# SecurityNode.net
KiCad netlist of a schematic drawn in Altium Designer
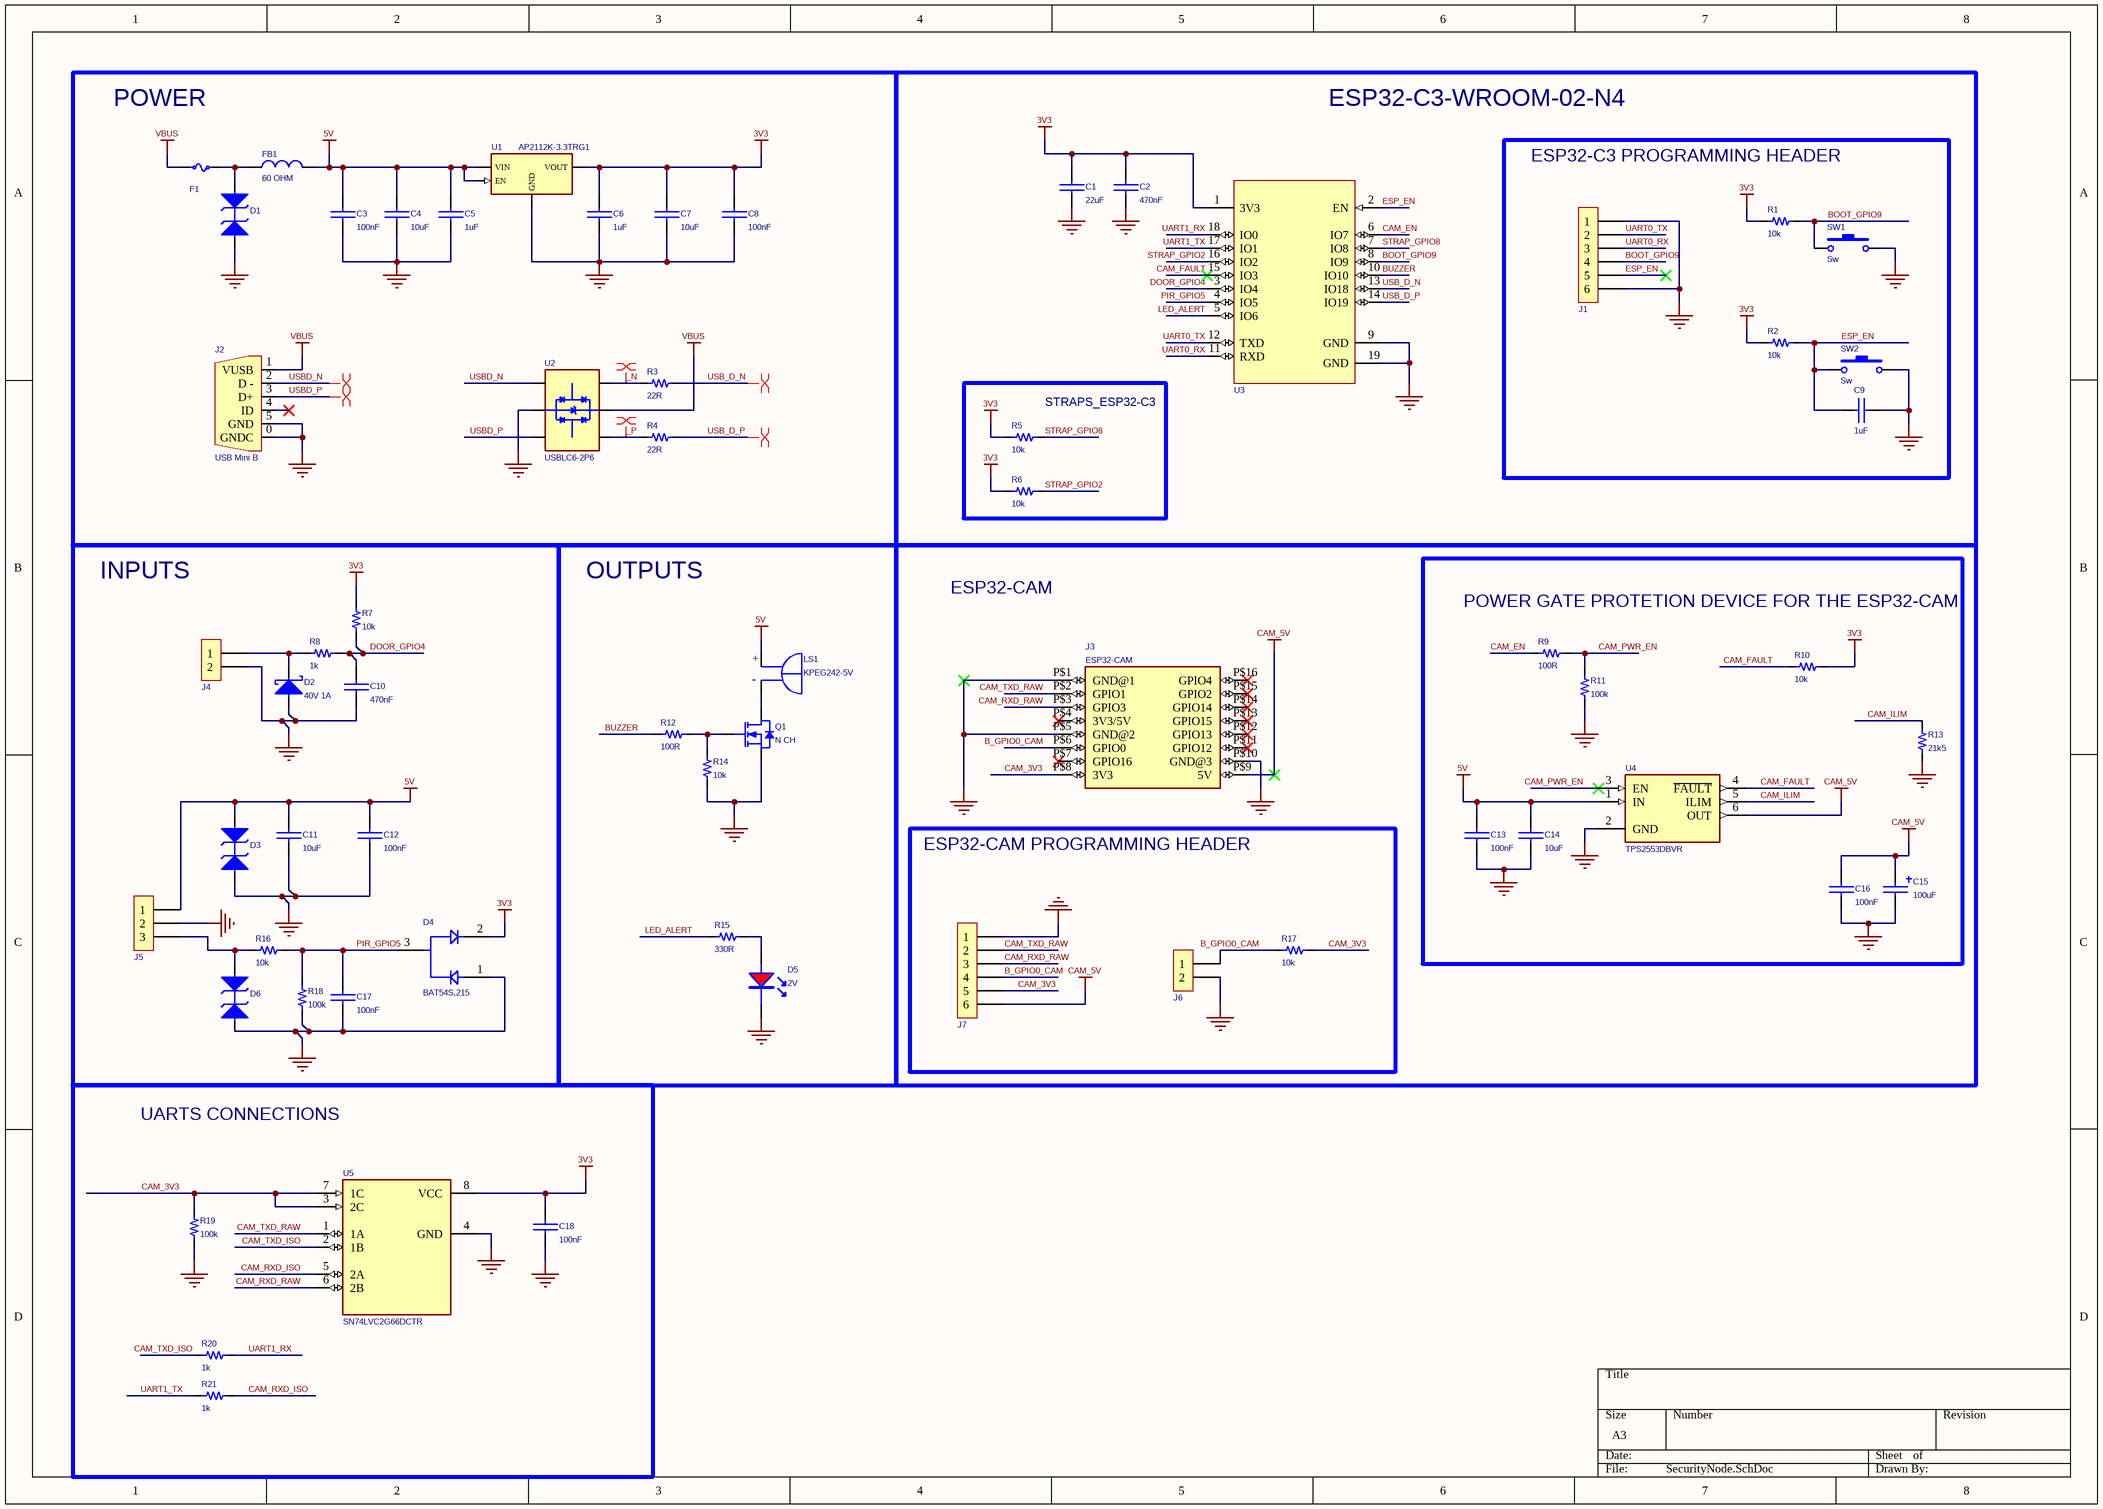
[diagram p0: SecurityNode.SchDoc]

(export (version "E")
  (design (tool "Eeschema 10.0.6"))
  (components
    (comp (ref "C1")
      (value "22uF")
      (footprint "0805_cap")
      (description "16V 22uF X5R ±20% 0805 Multilayer Ceramic Capacitors MLCC - SMD/SMT ROHS")
      (fields
        (field (name "MANUFACTURER") "Chinocera")
        (field (name "MANUFACTURER PART NUMBER") "HGC0805R5226M160NSLJ")
      )
      (libsource (lib "SecurityNodeComponents") (part "Cap_22uF_0805_16V"))
    )
    (comp (ref "C2")
      (value "470nF")
      (footprint "0603_cap")
      (description "50V 470nF X7R ±10% 0603 Multilayer Ceramic Capacitors MLCC - SMD/SMT ROHS")
      (fields
        (field (name "MANUFACTURER") "Chinocera")
        (field (name "MANUFACTURER PART NUMBER") "HGC0603R7474K500NTHJ")
      )
      (libsource (lib "SecurityNodeComponents") (part "Cap_470nF_0603_50V"))
    )
    (comp (ref "C3")
      (value "100nF")
      (footprint "0603_cap")
      (description "100nF ±20% 6.3V Ceramic Capacitor X5R 0201")
      (fields
        (field (name "MANUFACTURER") "HRE")
        (field (name "MANUFACTURER PART NUMBER") "CGA0201X5R104M6R3ET")
      )
      (libsource (lib "SecurityNodeComponents") (part "Cap_100nF_0603_6.3V"))
    )
    (comp (ref "C4")
      (value "10uF")
      (footprint "0603_cap")
      (description "10V 10uF X5R ±10% 0603 Multilayer Ceramic Capacitors MLCC - SMD/SMT ROHS")
      (fields
        (field (name "MANUFACTURER") "CCTC")
        (field (name "MANUFACTURER PART NUMBER") "TCC0603X5R106K100CT")
      )
      (libsource (lib "SecurityNodeComponents") (part "Cap_10uF_0603_10V"))
    )
    (comp (ref "C5")
      (value "1uF")
      (footprint "0603_cap")
      (description "50V 1uF X5R ±10% 0603 Multilayer Ceramic Capacitors MLCC - SMD/SMT ROHS")
      (fields
        (field (name "MANUFACTURER") "Samsung Electro-Mechanics")
        (field (name "MANUFACTURER PART NUMBER") "CL10A105KB8NNNC")
      )
      (libsource (lib "SecurityNodeComponents") (part "Cap_1uF_0603_50V"))
    )
    (comp (ref "C6")
      (value "1uF")
      (footprint "0603_cap")
      (description "50V 1uF X5R ±10% 0603 Multilayer Ceramic Capacitors MLCC - SMD/SMT ROHS")
      (fields
        (field (name "MANUFACTURER") "Samsung Electro-Mechanics")
        (field (name "MANUFACTURER PART NUMBER") "CL10A105KB8NNNC")
      )
      (libsource (lib "SecurityNodeComponents") (part "Cap_1uF_0603_50V"))
    )
    (comp (ref "C7")
      (value "10uF")
      (footprint "0603_cap")
      (description "10V 10uF X5R ±10% 0603 Multilayer Ceramic Capacitors MLCC - SMD/SMT ROHS")
      (fields
        (field (name "MANUFACTURER") "CCTC")
        (field (name "MANUFACTURER PART NUMBER") "TCC0603X5R106K100CT")
      )
      (libsource (lib "SecurityNodeComponents") (part "Cap_10uF_0603_10V"))
    )
    (comp (ref "C8")
      (value "100nF")
      (footprint "0603_cap")
      (description "100nF ±20% 6.3V Ceramic Capacitor X5R 0201")
      (fields
        (field (name "MANUFACTURER") "HRE")
        (field (name "MANUFACTURER PART NUMBER") "CGA0201X5R104M6R3ET")
      )
      (libsource (lib "SecurityNodeComponents") (part "Cap_100nF_0603_6.3V"))
    )
    (comp (ref "C9")
      (value "1uF")
      (footprint "0603_cap")
      (description "50V 1uF X5R ±10% 0603 Multilayer Ceramic Capacitors MLCC - SMD/SMT ROHS")
      (fields
        (field (name "MANUFACTURER") "Samsung Electro-Mechanics")
        (field (name "MANUFACTURER PART NUMBER") "CL10A105KB8NNNC")
      )
      (libsource (lib "SecurityNodeComponents") (part "Cap_1uF_0603_50V"))
    )
    (comp (ref "C10")
      (value "470nF")
      (footprint "0603_cap")
      (description "50V 470nF X7R ±10% 0603 Multilayer Ceramic Capacitors MLCC - SMD/SMT ROHS")
      (fields
        (field (name "MANUFACTURER") "Chinocera")
        (field (name "MANUFACTURER PART NUMBER") "HGC0603R7474K500NTHJ")
      )
      (libsource (lib "SecurityNodeComponents") (part "Cap_470nF_0603_50V"))
    )
    (comp (ref "C11")
      (value "10uF")
      (footprint "0603_cap")
      (description "10V 10uF X5R ±10% 0603 Multilayer Ceramic Capacitors MLCC - SMD/SMT ROHS")
      (fields
        (field (name "MANUFACTURER") "CCTC")
        (field (name "MANUFACTURER PART NUMBER") "TCC0603X5R106K100CT")
      )
      (libsource (lib "SecurityNodeComponents") (part "Cap_10uF_0603_10V"))
    )
    (comp (ref "C12")
      (value "100nF")
      (footprint "0603_cap")
      (description "100nF ±20% 6.3V Ceramic Capacitor X5R 0201")
      (fields
        (field (name "MANUFACTURER") "HRE")
        (field (name "MANUFACTURER PART NUMBER") "CGA0201X5R104M6R3ET")
      )
      (libsource (lib "SecurityNodeComponents") (part "Cap_100nF_0603_6.3V"))
    )
    (comp (ref "C13")
      (value "100nF")
      (footprint "0603_cap")
      (description "100nF ±20% 6.3V Ceramic Capacitor X5R 0201")
      (fields
        (field (name "MANUFACTURER") "HRE")
        (field (name "MANUFACTURER PART NUMBER") "CGA0201X5R104M6R3ET")
      )
      (libsource (lib "SecurityNodeComponents") (part "Cap_100nF_0603_6.3V"))
    )
    (comp (ref "C14")
      (value "10uF")
      (footprint "0603_cap")
      (description "10V 10uF X5R ±10% 0603 Multilayer Ceramic Capacitors MLCC - SMD/SMT ROHS")
      (fields
        (field (name "MANUFACTURER") "CCTC")
        (field (name "MANUFACTURER PART NUMBER") "TCC0603X5R106K100CT")
      )
      (libsource (lib "SecurityNodeComponents") (part "Cap_10uF_0603_10V"))
    )
    (comp (ref "C15")
      (value "100uF")
      (footprint "CAP_TH_2.5MM_6.3*12MM")
      (description "100uF 35V ±20% Plugin,D6.3xL12mm Aluminum Electrolytic Capacitors - Leaded ROHS")
      (fields (field (name "MANUFACTURER") "HRK") (field (name "MANUFACTURER PART NUMBER") "35V100uF CD110"))
      (libsource (lib "SecurityNodeComponents") (part "Cap_100uF_ALU_TH_35V"))
    )
    (comp (ref "C16")
      (value "100nF")
      (footprint "0603_cap")
      (description "100nF ±20% 6.3V Ceramic Capacitor X5R 0201")
      (fields
        (field (name "MANUFACTURER") "HRE")
        (field (name "MANUFACTURER PART NUMBER") "CGA0201X5R104M6R3ET")
      )
      (libsource (lib "SecurityNodeComponents") (part "Cap_100nF_0603_6.3V"))
    )
    (comp (ref "C17")
      (value "100nF")
      (footprint "0603_cap")
      (description "100nF ±20% 6.3V Ceramic Capacitor X5R 0201")
      (fields
        (field (name "MANUFACTURER") "HRE")
        (field (name "MANUFACTURER PART NUMBER") "CGA0201X5R104M6R3ET")
      )
      (libsource (lib "SecurityNodeComponents") (part "Cap_100nF_0603_6.3V"))
    )
    (comp (ref "C18")
      (value "100nF")
      (footprint "0603_cap")
      (description "100nF ±20% 6.3V Ceramic Capacitor X5R 0201")
      (fields
        (field (name "MANUFACTURER") "HRE")
        (field (name "MANUFACTURER PART NUMBER") "CGA0201X5R104M6R3ET")
      )
      (libsource (lib "SecurityNodeComponents") (part "Cap_100nF_0603_6.3V"))
    )
    (comp (ref "D1")
      (value "TVS 12V")
      (footprint "SOD_123FL")
      (description "21.7A 200W@10/1000us 9.2V 7V Bidirectional 5V SOD-123FL ESD and Surge Protection (TVS/ESD) ROHS")
      (fields (field (name "MANUFACTURER") "TDSEMIC") (field (name "MANUFACTURER PART NUMBER") "SMF5.0CA"))
      (libsource (lib "SecurityNodeComponents") (part "TVS_5V_1CH_BID_SOD_123FL"))
    )
    (comp (ref "D2")
      (value "40V 1A")
      (footprint "SOD_123")
      (description "DIODE SCHOTTKY 40V 1A SOD123F")
      (fields
        (field (name "MANUFACTURER") "Shanghai Prisemi Elec")
        (field (name "MANUFACTURER PART NUMBER") "PSBD1DF40V1H")
      )
      (libsource (lib "SecurityNodeComponents") (part "D_Schottky_40V_1A_SOD_123F"))
    )
    (comp (ref "D3")
      (value "TVS 12V")
      (footprint "SOD_123FL")
      (description "21.7A 200W@10/1000us 9.2V 7V Bidirectional 5V SOD-123FL ESD and Surge Protection (TVS/ESD) ROHS")
      (fields (field (name "MANUFACTURER") "TDSEMIC") (field (name "MANUFACTURER PART NUMBER") "SMF5.0CA"))
      (libsource (lib "SecurityNodeComponents") (part "TVS_5V_1CH_BID_SOD_123FL"))
    )
    (comp (ref "D4")
      (value "BAT54S,215")
      (footprint "SOT23")
      (fields (field (name "MF") "Nexperia"))
      (libsource (lib "SecurityNodeComponents") (part "BAT54S,215"))
    )
    (comp (ref "D5")
      (value "2V")
      (footprint "0805_LED")
      (description "LED RED CLEAR 0805 SMD")
      (fields
        (field (name "MANUFACTURER") "XINGLIGHT")
        (field (name "MANUFACTURER PART NUMBER") "XL-2012SURC")
      )
      (libsource (lib "SecurityNodeComponents") (part "LED_0805_RED"))
    )
    (comp (ref "D6")
      (value "TVS 12V")
      (footprint "SOD_123FL")
      (description "21.7A 200W@10/1000us 9.2V 7V Bidirectional 5V SOD-123FL ESD and Surge Protection (TVS/ESD) ROHS")
      (fields (field (name "MANUFACTURER") "TDSEMIC") (field (name "MANUFACTURER PART NUMBER") "SMF5.0CA"))
      (libsource (lib "SecurityNodeComponents") (part "TVS_5V_1CH_BID_SOD_123FL"))
    )
    (comp (ref "F1")
      (value "YTL 1206L075/16V")
      (footprint "FUSC1608X31N")
      (description "16V 750mA 100A 1.5A 90mΩ 1206 PTC Resettable Fuses RoHS")
      (fields
        (field (name "MANUFACTURER PART NUMBER") "1206L075/16V")
        (field (name "MANUFACTURER") "Littelfuse Inc")
      )
      (libsource (lib "SecurityNodeComponents") (part "YTL 1206L075/16V"))
    )
    (comp (ref "FB1")
      (value "60 OHM")
      (footprint "0603_fb")
      (description "2A 1 100mΩ 60Ω@100MHz ±25% 0603 Ferrite Beads ROHS")
      (fields
        (field (name "MANUFACTURER") "TAI-TECH")
        (field (name "MANUFACTURER PART NUMBER") "HCB1608KF-600T20")
      )
      (libsource (lib "SecurityNodeComponents") (part "FB_60_0603_2A"))
    )
    (comp (ref "J1")
      (value "6x1")
      (footprint "H_6x1_TH_100mil")
      (description "H_Male_6x1_TH_100mil")
      (libsource (lib "SecurityNodeComponents") (part "H_Male_6x1_TH_100mil"))
    )
    (comp (ref "J2")
      (value "USB Mini B")
      (footprint "CON_5x1_SMD_miniUSB_B")
      (description "CONN RCPT USB2.0 MINI B SMD R/A")
      (fields
        (field (name "MANUFACTURER PART NUMBER") "KH-MINI-SMT-5P-Cu")
        (field (name "MANUFACTURER") "EDAC Inc.")
      )
      (libsource (lib "SecurityNodeComponents") (part "Con_Mini_USB_B"))
    )
    (comp (ref "J3")
      (value "ESP32-CAM")
      (footprint "ESP32-CAM")
      (fields (field (name "MF") "AI-Thinker"))
      (libsource (lib "SecurityNodeComponents") (part "ESP32-CAM"))
    )
    (comp (ref "J4")
      (value "2x1")
      (footprint "H_2x1_TH_100mil")
      (description "H_Male_2x1_TH_100mil")
      (libsource (lib "SecurityNodeComponents") (part "H_Male_2x1_TH_100mil"))
    )
    (comp (ref "J5")
      (value "3x1")
      (footprint "H_3X1_TH_100mil")
      (description "H_Male_3x1_TH_100mil")
      (libsource (lib "SecurityNodeComponents") (part "H_Male_3x1_TH_100mil"))
    )
    (comp (ref "J6")
      (value "2x1")
      (footprint "H_2x1_TH_100mil")
      (description "H_Male_2x1_TH_100mil")
      (libsource (lib "SecurityNodeComponents") (part "H_Male_2x1_TH_100mil"))
    )
    (comp (ref "J7")
      (value "6x1")
      (footprint "H_6x1_TH_100mil")
      (description "H_Male_6x1_TH_100mil")
      (libsource (lib "SecurityNodeComponents") (part "H_Male_6x1_TH_100mil"))
    )
    (comp (ref "LS1")
      (value "KPEG242-5V")
      (footprint "XDCR_KPEG242-5V - duplicate")
      (libsource (lib "SecurityNodeComponents") (part "KPEG242-5V"))
    )
    (comp (ref "Q1")
      (value "N CH")
      (footprint "SOT_23_3")
      (description "MOSFET N-CH 20V SOT23")
      (fields (field (name "MANUFACTURER") "Doeshare") (field (name "MANUFACTURER PART NUMBER") "DN2302S"))
      (libsource (lib "SecurityNodeComponents") (part "Q_NFET_20V_3.2A_SOT23"))
    )
    (comp (ref "R1")
      (value "10k")
      (footprint "0603_res")
      (description "RES SMD 10k OHM 5% 1/10W 0603")
      (fields (field (name "MANUFACTURER") "FOJAN") (field (name "MANUFACTURER PART NUMBER") "FRC0603J103TS"))
      (libsource (lib "SecurityNodeComponents") (part "Res_10k_0603_1/10W"))
    )
    (comp (ref "R2")
      (value "10k")
      (footprint "0603_res")
      (description "RES SMD 10k OHM 5% 1/10W 0603")
      (fields (field (name "MANUFACTURER") "FOJAN") (field (name "MANUFACTURER PART NUMBER") "FRC0603J103TS"))
      (libsource (lib "SecurityNodeComponents") (part "Res_10k_0603_1/10W"))
    )
    (comp (ref "R3")
      (value "22R")
      (footprint "0603_res")
      (description "100mW 22Ω 75V Thick Film Resistor ±100ppm/℃ ±1% 0603 Chip Resistor - Surface Mount RoHS")
      (fields
        (field (name "MANUFACTURER") "UNI-ROYAL")
        (field (name "MANUFACTURER PART NUMBER") "0603WAF220JT5E")
      )
      (libsource (lib "SecurityNodeComponents") (part "Res_22R_0603_1/10W"))
    )
    (comp (ref "R4")
      (value "22R")
      (footprint "0603_res")
      (description "100mW 22Ω 75V Thick Film Resistor ±100ppm/℃ ±1% 0603 Chip Resistor - Surface Mount RoHS")
      (fields
        (field (name "MANUFACTURER") "UNI-ROYAL")
        (field (name "MANUFACTURER PART NUMBER") "0603WAF220JT5E")
      )
      (libsource (lib "SecurityNodeComponents") (part "Res_22R_0603_1/10W"))
    )
    (comp (ref "R5")
      (value "10k")
      (footprint "0603_res")
      (description "RES SMD 10k OHM 5% 1/10W 0603")
      (fields (field (name "MANUFACTURER") "FOJAN") (field (name "MANUFACTURER PART NUMBER") "FRC0603J103TS"))
      (libsource (lib "SecurityNodeComponents") (part "Res_10k_0603_1/10W"))
    )
    (comp (ref "R6")
      (value "10k")
      (footprint "0603_res")
      (description "RES SMD 10k OHM 5% 1/10W 0603")
      (fields (field (name "MANUFACTURER") "FOJAN") (field (name "MANUFACTURER PART NUMBER") "FRC0603J103TS"))
      (libsource (lib "SecurityNodeComponents") (part "Res_10k_0603_1/10W"))
    )
    (comp (ref "R7")
      (value "10k")
      (footprint "0603_res")
      (description "RES SMD 10k OHM 5% 1/10W 0603")
      (fields (field (name "MANUFACTURER") "FOJAN") (field (name "MANUFACTURER PART NUMBER") "FRC0603J103TS"))
      (libsource (lib "SecurityNodeComponents") (part "Res_10k_0603_1/10W"))
    )
    (comp (ref "R8")
      (value "1k")
      (footprint "0603_res")
      (description "RES SMD 1k OHM 5% 1/10W 0603")
      (fields
        (field (name "MANUFACTURER") "FOJAN")
        (field (name "MANUFACTURER PART NUMBER") "FRC0603J102 TS")
      )
      (libsource (lib "SecurityNodeComponents") (part "Res_1k_0603_1/10W"))
    )
    (comp (ref "R9")
      (value "100R")
      (footprint "0603_res")
      (description "RES SMD 100R OHM 5% 1/10W 0603")
      (fields
        (field (name "MANUFACTURER") "FOJAN")
        (field (name "MANUFACTURER PART NUMBER") "FRC0603J101 TS")
      )
      (libsource (lib "SecurityNodeComponents") (part "Res_100R_0603_1/10W"))
    )
    (comp (ref "R10")
      (value "10k")
      (footprint "0603_res")
      (description "RES SMD 10k OHM 5% 1/10W 0603")
      (fields (field (name "MANUFACTURER") "FOJAN") (field (name "MANUFACTURER PART NUMBER") "FRC0603J103TS"))
      (libsource (lib "SecurityNodeComponents") (part "Res_10k_0603_1/10W"))
    )
    (comp (ref "R11")
      (value "100k")
      (footprint "0603_res")
      (description "100mW 100kΩ 75V Thick Film Resistor ±100ppm/℃ ±1% 0603 Chip Resistor - Surface Mount RoHS")
      (fields
        (field (name "MANUFACTURER") "YAGEO")
        (field (name "MANUFACTURER PART NUMBER") "RC0603FR-07100KL")
      )
      (libsource (lib "SecurityNodeComponents") (part "Res_100k_0603_1/8W"))
    )
    (comp (ref "R12")
      (value "100R")
      (footprint "0603_res")
      (description "RES SMD 100R OHM 5% 1/10W 0603")
      (fields
        (field (name "MANUFACTURER") "FOJAN")
        (field (name "MANUFACTURER PART NUMBER") "FRC0603J101 TS")
      )
      (libsource (lib "SecurityNodeComponents") (part "Res_100R_0603_1/10W"))
    )
    (comp (ref "R13")
      (value "21k5")
      (footprint "0603_res")
      (description "21.5kΩ 100mW 75V Thick Film Resistor ±100ppm/℃ ±1% 0603 Chip Resistor - Surface Mount RoHS")
      (fields
        (field (name "MANUFACTURER") "YAGEO")
        (field (name "MANUFACTURER PART NUMBER") "RC0603FR-0721K5L")
      )
      (libsource (lib "SecurityNodeComponents") (part "Res_21k5_0603_1/10W"))
    )
    (comp (ref "R14")
      (value "10k")
      (footprint "0603_res")
      (description "RES SMD 10k OHM 5% 1/10W 0603")
      (fields (field (name "MANUFACTURER") "FOJAN") (field (name "MANUFACTURER PART NUMBER") "FRC0603J103TS"))
      (libsource (lib "SecurityNodeComponents") (part "Res_10k_0603_1/10W"))
    )
    (comp (ref "R15")
      (value "330R")
      (footprint "0603_res")
      (description "RES SMD 330R OHM 5% 1/10W 0603")
      (fields
        (field (name "MANUFACTURER") "FOJAN")
        (field (name "MANUFACTURER PART NUMBER") "FRC0603J331 TS")
      )
      (libsource (lib "SecurityNodeComponents") (part "Res_330R_0603_1/10W"))
    )
    (comp (ref "R16")
      (value "10k")
      (footprint "0603_res")
      (description "RES SMD 10k OHM 5% 1/10W 0603")
      (fields (field (name "MANUFACTURER") "FOJAN") (field (name "MANUFACTURER PART NUMBER") "FRC0603J103TS"))
      (libsource (lib "SecurityNodeComponents") (part "Res_10k_0603_1/10W"))
    )
    (comp (ref "R17")
      (value "10k")
      (footprint "0603_res")
      (description "RES SMD 10k OHM 5% 1/10W 0603")
      (fields (field (name "MANUFACTURER") "FOJAN") (field (name "MANUFACTURER PART NUMBER") "FRC0603J103TS"))
      (libsource (lib "SecurityNodeComponents") (part "Res_10k_0603_1/10W"))
    )
    (comp (ref "R18")
      (value "100k")
      (footprint "0603_res")
      (description "100mW 100kΩ 75V Thick Film Resistor ±100ppm/℃ ±1% 0603 Chip Resistor - Surface Mount RoHS")
      (fields
        (field (name "MANUFACTURER") "YAGEO")
        (field (name "MANUFACTURER PART NUMBER") "RC0603FR-07100KL")
      )
      (libsource (lib "SecurityNodeComponents") (part "Res_100k_0603_1/8W"))
    )
    (comp (ref "R19")
      (value "100k")
      (footprint "0603_res")
      (description "100mW 100kΩ 75V Thick Film Resistor ±100ppm/℃ ±1% 0603 Chip Resistor - Surface Mount RoHS")
      (fields
        (field (name "MANUFACTURER") "YAGEO")
        (field (name "MANUFACTURER PART NUMBER") "RC0603FR-07100KL")
      )
      (libsource (lib "SecurityNodeComponents") (part "Res_100k_0603_1/8W"))
    )
    (comp (ref "R20")
      (value "1k")
      (footprint "0603_res")
      (description "RES SMD 1k OHM 5% 1/10W 0603")
      (fields
        (field (name "MANUFACTURER") "FOJAN")
        (field (name "MANUFACTURER PART NUMBER") "FRC0603J102 TS")
      )
      (libsource (lib "SecurityNodeComponents") (part "Res_1k_0603_1/10W"))
    )
    (comp (ref "R21")
      (value "1k")
      (footprint "0603_res")
      (description "RES SMD 1k OHM 5% 1/10W 0603")
      (fields
        (field (name "MANUFACTURER") "FOJAN")
        (field (name "MANUFACTURER PART NUMBER") "FRC0603J102 TS")
      )
      (libsource (lib "SecurityNodeComponents") (part "Res_1k_0603_1/10W"))
    )
    (comp (ref "SW1")
      (value "Sw")
      (footprint "Sw_PUSH_4.5x4.5x5mm")
      (description "SWITCH TACTILE SPST-NO 0.05A 12V")
      (fields
        (field (name "MANUFACTURER") "BZCN")
        (field (name "MANUFACTURER PART NUMBER") "TSC015A05026A")
        (field (name "LAST MODIFIED BY") "N-A.Potosi")
      )
      (libsource (lib "SecurityNodeComponents") (part "Sw_PUSH_4.5x4.5x5.0xmm"))
    )
    (comp (ref "SW2")
      (value "Sw")
      (footprint "Sw_PUSH_4.5x4.5x5mm")
      (description "SWITCH TACTILE SPST-NO 0.05A 12V")
      (fields
        (field (name "MANUFACTURER") "BZCN")
        (field (name "MANUFACTURER PART NUMBER") "TSC015A05026A")
        (field (name "LAST MODIFIED BY") "N-A.Potosi")
      )
      (libsource (lib "SecurityNodeComponents") (part "Sw_PUSH_4.5x4.5x5.0xmm"))
    )
    (comp (ref "U1")
      (value "AP2112K-3.3TRG1")
      (footprint "SOT95P285X140-5N")
      (description "Linear Voltage Regulator IC Positive Fixed 1 Output 600mA SOT-25")
      (fields (field (name "MF") "Diodes Inc."))
      (libsource (lib "SecurityNodeComponents") (part "AP2112K-3.3TRG1"))
    )
    (comp (ref "U2")
      (value "USBLC6-2P6")
      (footprint "SOT50P160X60-6N")
      (description "17VC Clamp 5A@8/20us Ipp ESD DIODE SOT-666-6")
      (fields (field (name "MANUFACTURER") "ST"))
      (libsource (lib "SecurityNodeComponents") (part "USBLC6-2P6"))
    )
    (comp (ref "U3")
      (value "ESP32-C3-WROOM-02-N4")
      (footprint "ESP32-C3-WROOM-02-N4")
      (description "RF TXRX MOD BT WIFI PCB TH SMD")
      (fields (field (name "MANUFACTURER") "Espressif Systems"))
      (libsource (lib "SecurityNodeComponents") (part "MCU_ESP32-C3-WROOM-02-N4"))
    )
    (comp (ref "U4")
      (value "TPS2553DBVR")
      (footprint "SOT95P280X145-6N")
      (description "0.075-1.7A adj. ILIMIT, 2.5-6.5V, 85mÎ© USB power switch, active-high, reverse blocking")
      (fields (field (name "MF") "Texas Instruments"))
      (libsource (lib "SecurityNodeComponents") (part "TPS2553DBVR"))
    )
    (comp (ref "U5")
      (value "SN74LVC2G66DCTR")
      (footprint "SN74LVC2G66DCTR")
      (description "5-V, 1:1 (SPST), 2-channel general-purpose analog switch with low on-state resistance")
      (fields (field (name "MF") "Texas Instruments"))
      (libsource (lib "SecurityNodeComponents") (part "SN74LVC2G66DCTR"))
    )
  )
  (nets
    (net (code "1") (name "/BOOT_GPIO9") (class "Default")
      (node (ref "J1") (pin "4") (pinfunction "4_4") (pintype "passive"))
      (node (ref "R1") (pin "2") (pinfunction "2_2") (pintype "passive"))
      (node (ref "SW1") (pin "1") (pinfunction "1_1") (pintype "passive"))
      (node (ref "U3") (pin "8") (pinfunction "IO9_8") (pintype "bidirectional"))
    )
    (net (code "2") (name "/BUZZER") (class "Default")
      (node (ref "R12") (pin "1") (pinfunction "1_1") (pintype "passive"))
      (node (ref "U3") (pin "10") (pinfunction "IO10_10") (pintype "bidirectional"))
    )
    (net (code "3") (name "/B_GPIO0_CAM") (class "Default")
      (node (ref "J3") (pin "P$6") (pinfunction "GPIO0_P$6") (pintype "bidirectional"))
      (node (ref "J6") (pin "1") (pinfunction "1_1") (pintype "passive"))
      (node (ref "J7") (pin "4") (pinfunction "4_4") (pintype "passive"))
      (node (ref "R17") (pin "1") (pinfunction "1_1") (pintype "passive"))
    )
    (net (code "4") (name "/CAM_3V3") (class "Default")
      (node (ref "J3") (pin "P$8") (pinfunction "3V3_P$8") (pintype "bidirectional"))
      (node (ref "J7") (pin "5") (pinfunction "5_5") (pintype "passive"))
      (node (ref "R17") (pin "2") (pinfunction "2_2") (pintype "passive"))
      (node (ref "R19") (pin "2") (pinfunction "2_2") (pintype "passive"))
      (node (ref "U5") (pin "3") (pinfunction "2C_3") (pintype "input"))
      (node (ref "U5") (pin "7") (pinfunction "1C_7") (pintype "input"))
    )
    (net (code "5") (name "/CAM_EN") (class "Default")
      (node (ref "R9") (pin "1") (pinfunction "1_1") (pintype "passive"))
      (node (ref "U3") (pin "6") (pinfunction "IO7_6") (pintype "bidirectional"))
    )
    (net (code "6") (name "/CAM_FAULT") (class "Default")
      (node (ref "R10") (pin "1") (pinfunction "1_1") (pintype "passive"))
      (node (ref "U3") (pin "15") (pinfunction "IO3_15") (pintype "bidirectional"))
      (node (ref "U4") (pin "4") (pinfunction "~{FAULT}_4") (pintype "output"))
    )
    (net (code "7") (name "/CAM_ILIM") (class "Default")
      (node (ref "R13") (pin "1") (pinfunction "1_1") (pintype "passive"))
      (node (ref "U4") (pin "5") (pinfunction "ILIM_5") (pintype "output"))
    )
    (net (code "8") (name "/CAM_PWR_EN") (class "Default")
      (node (ref "R11") (pin "1") (pinfunction "1_1") (pintype "passive"))
      (node (ref "R9") (pin "2") (pinfunction "2_2") (pintype "passive"))
      (node (ref "U4") (pin "3") (pinfunction "EN_3") (pintype "input"))
    )
    (net (code "9") (name "/CAM_RXD_ISO") (class "Default")
      (node (ref "R21") (pin "2") (pinfunction "2_2") (pintype "passive"))
      (node (ref "U5") (pin "5") (pinfunction "2A_5") (pintype "bidirectional"))
    )
    (net (code "10") (name "/CAM_RXD_RAW") (class "Default")
      (node (ref "J3") (pin "P$3") (pinfunction "GPIO3_P$3") (pintype "bidirectional"))
      (node (ref "J7") (pin "3") (pinfunction "3_3") (pintype "passive"))
      (node (ref "U5") (pin "6") (pinfunction "2B_6") (pintype "bidirectional"))
    )
    (net (code "11") (name "/CAM_TXD_ISO") (class "Default")
      (node (ref "R20") (pin "1") (pinfunction "1_1") (pintype "passive"))
      (node (ref "U5") (pin "2") (pinfunction "1B_2") (pintype "bidirectional"))
    )
    (net (code "12") (name "/CAM_TXD_RAW") (class "Default")
      (node (ref "J3") (pin "P$2") (pinfunction "GPIO1_P$2") (pintype "bidirectional"))
      (node (ref "J7") (pin "2") (pinfunction "2_2") (pintype "passive"))
      (node (ref "U5") (pin "1") (pinfunction "1A_1") (pintype "bidirectional"))
    )
    (net (code "13") (name "/DOOR_GPIO4") (class "Default")
      (node (ref "C10") (pin "1") (pinfunction "1_1") (pintype "passive"))
      (node (ref "R7") (pin "1") (pinfunction "1_1") (pintype "passive"))
      (node (ref "R8") (pin "2") (pinfunction "2_2") (pintype "passive"))
      (node (ref "U3") (pin "3") (pinfunction "IO4_3") (pintype "bidirectional"))
    )
    (net (code "14") (name "/ESP_EN") (class "Default")
      (node (ref "C9") (pin "1") (pinfunction "1_1") (pintype "passive"))
      (node (ref "J1") (pin "5") (pinfunction "5_5") (pintype "passive"))
      (node (ref "R2") (pin "2") (pinfunction "2_2") (pintype "passive"))
      (node (ref "SW2") (pin "1") (pinfunction "1_1") (pintype "passive"))
      (node (ref "U3") (pin "2") (pinfunction "EN_2") (pintype "input"))
    )
    (net (code "15") (name "/LED_ALERT") (class "Default")
      (node (ref "R15") (pin "1") (pinfunction "1_1") (pintype "passive"))
      (node (ref "U3") (pin "5") (pinfunction "IO6_5") (pintype "bidirectional"))
    )
    (net (code "16") (name "/PIR_GPIO5") (class "Default")
      (node (ref "C17") (pin "1") (pinfunction "1_1") (pintype "passive"))
      (node (ref "D4") (pin "3") (pinfunction "3_3") (pintype "passive"))
      (node (ref "R16") (pin "1") (pinfunction "1_1") (pintype "passive"))
      (node (ref "R18") (pin "1") (pinfunction "1_1") (pintype "passive"))
      (node (ref "U3") (pin "4") (pinfunction "IO5_4") (pintype "bidirectional"))
    )
    (net (code "17") (name "/STRAP_GPIO2") (class "Default")
      (node (ref "R6") (pin "2") (pinfunction "2_2") (pintype "passive"))
      (node (ref "U3") (pin "16") (pinfunction "IO2_16") (pintype "bidirectional"))
    )
    (net (code "18") (name "/STRAP_GPIO8") (class "Default")
      (node (ref "R5") (pin "2") (pinfunction "2_2") (pintype "passive"))
      (node (ref "U3") (pin "7") (pinfunction "IO8_7") (pintype "bidirectional"))
    )
    (net (code "19") (name "/UART0_RX") (class "Default")
      (node (ref "J1") (pin "3") (pinfunction "3_3") (pintype "passive"))
      (node (ref "U3") (pin "11") (pinfunction "RXD_11") (pintype "bidirectional"))
    )
    (net (code "20") (name "/UART0_TX") (class "Default")
      (node (ref "J1") (pin "2") (pinfunction "2_2") (pintype "passive"))
      (node (ref "U3") (pin "12") (pinfunction "TXD_12") (pintype "bidirectional"))
    )
    (net (code "21") (name "/UART1_RX") (class "Default")
      (node (ref "R20") (pin "2") (pinfunction "2_2") (pintype "passive"))
      (node (ref "U3") (pin "18") (pinfunction "IO0_18") (pintype "bidirectional"))
    )
    (net (code "22") (name "/UART1_TX") (class "Default")
      (node (ref "R21") (pin "1") (pinfunction "1_1") (pintype "passive"))
      (node (ref "U3") (pin "17") (pinfunction "IO1_17") (pintype "bidirectional"))
    )
    (net (code "23") (name "/USBD_N") (class "Default")
      (node (ref "J2") (pin "2") (pinfunction "D_-_2") (pintype "passive"))
      (node (ref "U2") (pin "1") (pinfunction "I/O1_1_1") (pintype "bidirectional"))
    )
    (net (code "24") (name "/USBD_P") (class "Default")
      (node (ref "J2") (pin "3") (pinfunction "D+_3") (pintype "passive"))
      (node (ref "U2") (pin "3") (pinfunction "I/O2_1_3") (pintype "bidirectional"))
    )
    (net (code "25") (name "/USB_D_N") (class "Default")
      (node (ref "R3") (pin "2") (pinfunction "2_2") (pintype "passive"))
      (node (ref "U3") (pin "13") (pinfunction "IO18_13") (pintype "bidirectional"))
    )
    (net (code "26") (name "/USB_D_P") (class "Default")
      (node (ref "R4") (pin "2") (pinfunction "2_2") (pintype "passive"))
      (node (ref "U3") (pin "14") (pinfunction "IO19_14") (pintype "bidirectional"))
    )
    (net (code "27") (name "/_N") (class "Default")
      (node (ref "R3") (pin "1") (pinfunction "1_1") (pintype "passive"))
      (node (ref "U2") (pin "6") (pinfunction "I/O1_2_6") (pintype "bidirectional"))
    )
    (net (code "28") (name "/_P") (class "Default")
      (node (ref "R4") (pin "1") (pinfunction "1_1") (pintype "passive"))
      (node (ref "U2") (pin "4") (pinfunction "I/O2_2_4") (pintype "bidirectional"))
    )
    (net (code "29") (name "3V3") (class "Default")
      (node (ref "C1") (pin "1") (pinfunction "1_1") (pintype "passive"))
      (node (ref "C18") (pin "1") (pinfunction "1_1") (pintype "passive"))
      (node (ref "C2") (pin "1") (pinfunction "1_1") (pintype "passive"))
      (node (ref "C6") (pin "1") (pinfunction "1_1") (pintype "passive"))
      (node (ref "C7") (pin "1") (pinfunction "1_1") (pintype "passive"))
      (node (ref "C8") (pin "1") (pinfunction "1_1") (pintype "passive"))
      (node (ref "D4") (pin "2") (pinfunction "2_2") (pintype "passive"))
      (node (ref "R1") (pin "1") (pinfunction "1_1") (pintype "passive"))
      (node (ref "R10") (pin "2") (pinfunction "2_2") (pintype "passive"))
      (node (ref "R2") (pin "1") (pinfunction "1_1") (pintype "passive"))
      (node (ref "R5") (pin "1") (pinfunction "1_1") (pintype "passive"))
      (node (ref "R6") (pin "1") (pinfunction "1_1") (pintype "passive"))
      (node (ref "R7") (pin "2") (pinfunction "2_2") (pintype "passive"))
      (node (ref "U1") (pin "5") (pinfunction "VOUT_5") (pintype "power_in"))
      (node (ref "U3") (pin "1") (pinfunction "3V3_1") (pintype "power_in"))
      (node (ref "U5") (pin "8") (pinfunction "VCC_8") (pintype "power_in"))
    )
    (net (code "30") (name "5V") (class "Default")
      (node (ref "C11") (pin "1") (pinfunction "1_1") (pintype "passive"))
      (node (ref "C12") (pin "1") (pinfunction "1_1") (pintype "passive"))
      (node (ref "C13") (pin "1") (pinfunction "1_1") (pintype "passive"))
      (node (ref "C14") (pin "1") (pinfunction "1_1") (pintype "passive"))
      (node (ref "C3") (pin "1") (pinfunction "1_1") (pintype "passive"))
      (node (ref "C4") (pin "1") (pinfunction "1_1") (pintype "passive"))
      (node (ref "C5") (pin "1") (pinfunction "1_1") (pintype "passive"))
      (node (ref "D3") (pin "1") (pinfunction "1_1") (pintype "passive"))
      (node (ref "FB1") (pin "2") (pinfunction "2_2") (pintype "passive"))
      (node (ref "J5") (pin "1") (pinfunction "1_1") (pintype "passive"))
      (node (ref "LS1") (pin "P") (pinfunction "POS_P") (pintype "passive"))
      (node (ref "U1") (pin "1") (pinfunction "VIN_1") (pintype "power_in"))
      (node (ref "U1") (pin "3") (pinfunction "EN_3") (pintype "input"))
      (node (ref "U4") (pin "1") (pinfunction "IN_1") (pintype "input"))
    )
    (net (code "31") (name "CAM_5V") (class "Default")
      (node (ref "C15") (pin "1") (pinfunction "1_1") (pintype "passive"))
      (node (ref "C16") (pin "1") (pinfunction "1_1") (pintype "passive"))
      (node (ref "J3") (pin "P$9") (pinfunction "5V_P$9") (pintype "bidirectional"))
      (node (ref "J7") (pin "6") (pinfunction "6_6") (pintype "passive"))
      (node (ref "U4") (pin "6") (pinfunction "OUT_6") (pintype "output"))
    )
    (net (code "32") (name "GND") (class "Default")
      (node (ref "C1") (pin "2") (pinfunction "2_2") (pintype "passive"))
      (node (ref "C10") (pin "2") (pinfunction "2_2") (pintype "passive"))
      (node (ref "C11") (pin "2") (pinfunction "2_2") (pintype "passive"))
      (node (ref "C12") (pin "2") (pinfunction "2_2") (pintype "passive"))
      (node (ref "C13") (pin "2") (pinfunction "2_2") (pintype "passive"))
      (node (ref "C14") (pin "2") (pinfunction "2_2") (pintype "passive"))
      (node (ref "C15") (pin "2") (pinfunction "2_2") (pintype "passive"))
      (node (ref "C16") (pin "2") (pinfunction "2_2") (pintype "passive"))
      (node (ref "C17") (pin "2") (pinfunction "2_2") (pintype "passive"))
      (node (ref "C18") (pin "2") (pinfunction "2_2") (pintype "passive"))
      (node (ref "C2") (pin "2") (pinfunction "2_2") (pintype "passive"))
      (node (ref "C3") (pin "2") (pinfunction "2_2") (pintype "passive"))
      (node (ref "C4") (pin "2") (pinfunction "2_2") (pintype "passive"))
      (node (ref "C5") (pin "2") (pinfunction "2_2") (pintype "passive"))
      (node (ref "C6") (pin "2") (pinfunction "2_2") (pintype "passive"))
      (node (ref "C7") (pin "2") (pinfunction "2_2") (pintype "passive"))
      (node (ref "C8") (pin "2") (pinfunction "2_2") (pintype "passive"))
      (node (ref "C9") (pin "2") (pinfunction "2_2") (pintype "passive"))
      (node (ref "D1") (pin "2") (pinfunction "2_2") (pintype "passive"))
      (node (ref "D2") (pin "2") (pinfunction "2_2") (pintype "passive"))
      (node (ref "D3") (pin "2") (pinfunction "2_2") (pintype "passive"))
      (node (ref "D4") (pin "1") (pinfunction "1_1") (pintype "passive"))
      (node (ref "D5") (pin "2") (pinfunction "2_2") (pintype "passive"))
      (node (ref "D6") (pin "2") (pinfunction "2_2") (pintype "passive"))
      (node (ref "J1") (pin "1") (pinfunction "1_1") (pintype "passive"))
      (node (ref "J1") (pin "6") (pinfunction "6_6") (pintype "passive"))
      (node (ref "J2") (pin "0") (pinfunction "GNDC_0") (pintype "passive"))
      (node (ref "J2") (pin "5") (pinfunction "GND_5") (pintype "passive"))
      (node (ref "J3") (pin "P$1") (pinfunction "GND@1_P$1") (pintype "bidirectional"))
      (node (ref "J3") (pin "P$10") (pinfunction "GND@3_P$10") (pintype "bidirectional"))
      (node (ref "J3") (pin "P$5") (pinfunction "GND@2_P$5") (pintype "bidirectional"))
      (node (ref "J4") (pin "2") (pinfunction "2_2") (pintype "passive"))
      (node (ref "J5") (pin "2") (pinfunction "2_2") (pintype "passive"))
      (node (ref "J6") (pin "2") (pinfunction "2_2") (pintype "passive"))
      (node (ref "J7") (pin "1") (pinfunction "1_1") (pintype "passive"))
      (node (ref "Q1") (pin "2") (pinfunction "S_2") (pintype "passive"))
      (node (ref "R11") (pin "2") (pinfunction "2_2") (pintype "passive"))
      (node (ref "R13") (pin "2") (pinfunction "2_2") (pintype "passive"))
      (node (ref "R14") (pin "1") (pinfunction "1_1") (pintype "passive"))
      (node (ref "R18") (pin "2") (pinfunction "2_2") (pintype "passive"))
      (node (ref "R19") (pin "1") (pinfunction "1_1") (pintype "passive"))
      (node (ref "SW1") (pin "2") (pinfunction "2_2") (pintype "passive"))
      (node (ref "SW2") (pin "2") (pinfunction "2_2") (pintype "passive"))
      (node (ref "U1") (pin "2") (pinfunction "GND_2") (pintype "power_in"))
      (node (ref "U2") (pin "2") (pinfunction "GND_2") (pintype "power_in"))
      (node (ref "U3") (pin "19") (pinfunction "GND_19") (pintype "power_in"))
      (node (ref "U3") (pin "9") (pinfunction "GND_9") (pintype "power_in"))
      (node (ref "U4") (pin "2") (pinfunction "GND_2") (pintype "power_in"))
      (node (ref "U5") (pin "4") (pinfunction "GND_4") (pintype "power_in"))
    )
    (net (code "33") (name "Net-(D1-Pad1)") (class "Default")
      (node (ref "D1") (pin "1") (pinfunction "1_1") (pintype "passive"))
      (node (ref "F1") (pin "2") (pinfunction "2_2") (pintype "passive"))
      (node (ref "FB1") (pin "1") (pinfunction "1_1") (pintype "passive"))
    )
    (net (code "34") (name "Net-(D2-Pad1)") (class "Default")
      (node (ref "D2") (pin "1") (pinfunction "1_1") (pintype "passive"))
      (node (ref "J4") (pin "1") (pinfunction "1_1") (pintype "passive"))
      (node (ref "R8") (pin "1") (pinfunction "1_1") (pintype "passive"))
    )
    (net (code "35") (name "Net-(D5-A)") (class "Default")
      (node (ref "D5") (pin "1") (pinfunction "A_1") (pintype "passive"))
      (node (ref "R15") (pin "2") (pinfunction "2_2") (pintype "passive"))
    )
    (net (code "36") (name "Net-(D6-Pad1)") (class "Default")
      (node (ref "D6") (pin "1") (pinfunction "1_1") (pintype "passive"))
      (node (ref "J5") (pin "3") (pinfunction "3_3") (pintype "passive"))
      (node (ref "R16") (pin "2") (pinfunction "2_2") (pintype "passive"))
    )
    (net (code "37") (name "Net-(LS1-NEG)") (class "Default")
      (node (ref "LS1") (pin "N") (pinfunction "NEG_N") (pintype "passive"))
      (node (ref "Q1") (pin "3") (pinfunction "D_3") (pintype "passive"))
    )
    (net (code "38") (name "Net-(Q1-G)") (class "Default")
      (node (ref "Q1") (pin "1") (pinfunction "G_1") (pintype "passive"))
      (node (ref "R12") (pin "2") (pinfunction "2_2") (pintype "passive"))
      (node (ref "R14") (pin "2") (pinfunction "2_2") (pintype "passive"))
    )
    (net (code "39") (name "VBUS") (class "Default")
      (node (ref "F1") (pin "1") (pinfunction "1_1") (pintype "passive"))
      (node (ref "J2") (pin "1") (pinfunction "VUSB_1") (pintype "passive"))
      (node (ref "U2") (pin "5") (pinfunction "VBUS_5") (pintype "power_in"))
    )
    (net (code "40") (name "unconnected-(J2-ID-Pad4)") (class "Default")
      (node (ref "J2") (pin "4") (pinfunction "ID_4") (pintype "passive+no_connect"))
    )
    (net (code "41") (name "unconnected-(J3-3V3{slash}5V-PadP$4)") (class "Default")
      (node (ref "J3") (pin "P$4") (pinfunction "3V3/5V_P$4") (pintype "bidirectional+no_connect"))
    )
    (net (code "42") (name "unconnected-(J3-GPIO2-PadP$15)") (class "Default")
      (node (ref "J3") (pin "P$15") (pinfunction "GPIO2_P$15") (pintype "bidirectional+no_connect"))
    )
    (net (code "43") (name "unconnected-(J3-GPIO4-PadP$16)") (class "Default")
      (node (ref "J3") (pin "P$16") (pinfunction "GPIO4_P$16") (pintype "bidirectional+no_connect"))
    )
    (net (code "44") (name "unconnected-(J3-GPIO12-PadP$11)") (class "Default")
      (node (ref "J3") (pin "P$11") (pinfunction "GPIO12_P$11") (pintype "bidirectional+no_connect"))
    )
    (net (code "45") (name "unconnected-(J3-GPIO13-PadP$12)") (class "Default")
      (node (ref "J3") (pin "P$12") (pinfunction "GPIO13_P$12") (pintype "bidirectional+no_connect"))
    )
    (net (code "46") (name "unconnected-(J3-GPIO14-PadP$14)") (class "Default")
      (node (ref "J3") (pin "P$14") (pinfunction "GPIO14_P$14") (pintype "bidirectional+no_connect"))
    )
    (net (code "47") (name "unconnected-(J3-GPIO15-PadP$13)") (class "Default")
      (node (ref "J3") (pin "P$13") (pinfunction "GPIO15_P$13") (pintype "bidirectional+no_connect"))
    )
    (net (code "48") (name "unconnected-(J3-GPIO16-PadP$7)") (class "Default")
      (node (ref "J3") (pin "P$7") (pinfunction "GPIO16_P$7") (pintype "bidirectional+no_connect"))
    )
  )
)
